# UART.net
KiCad netlist of a schematic drawn in Altium Designer
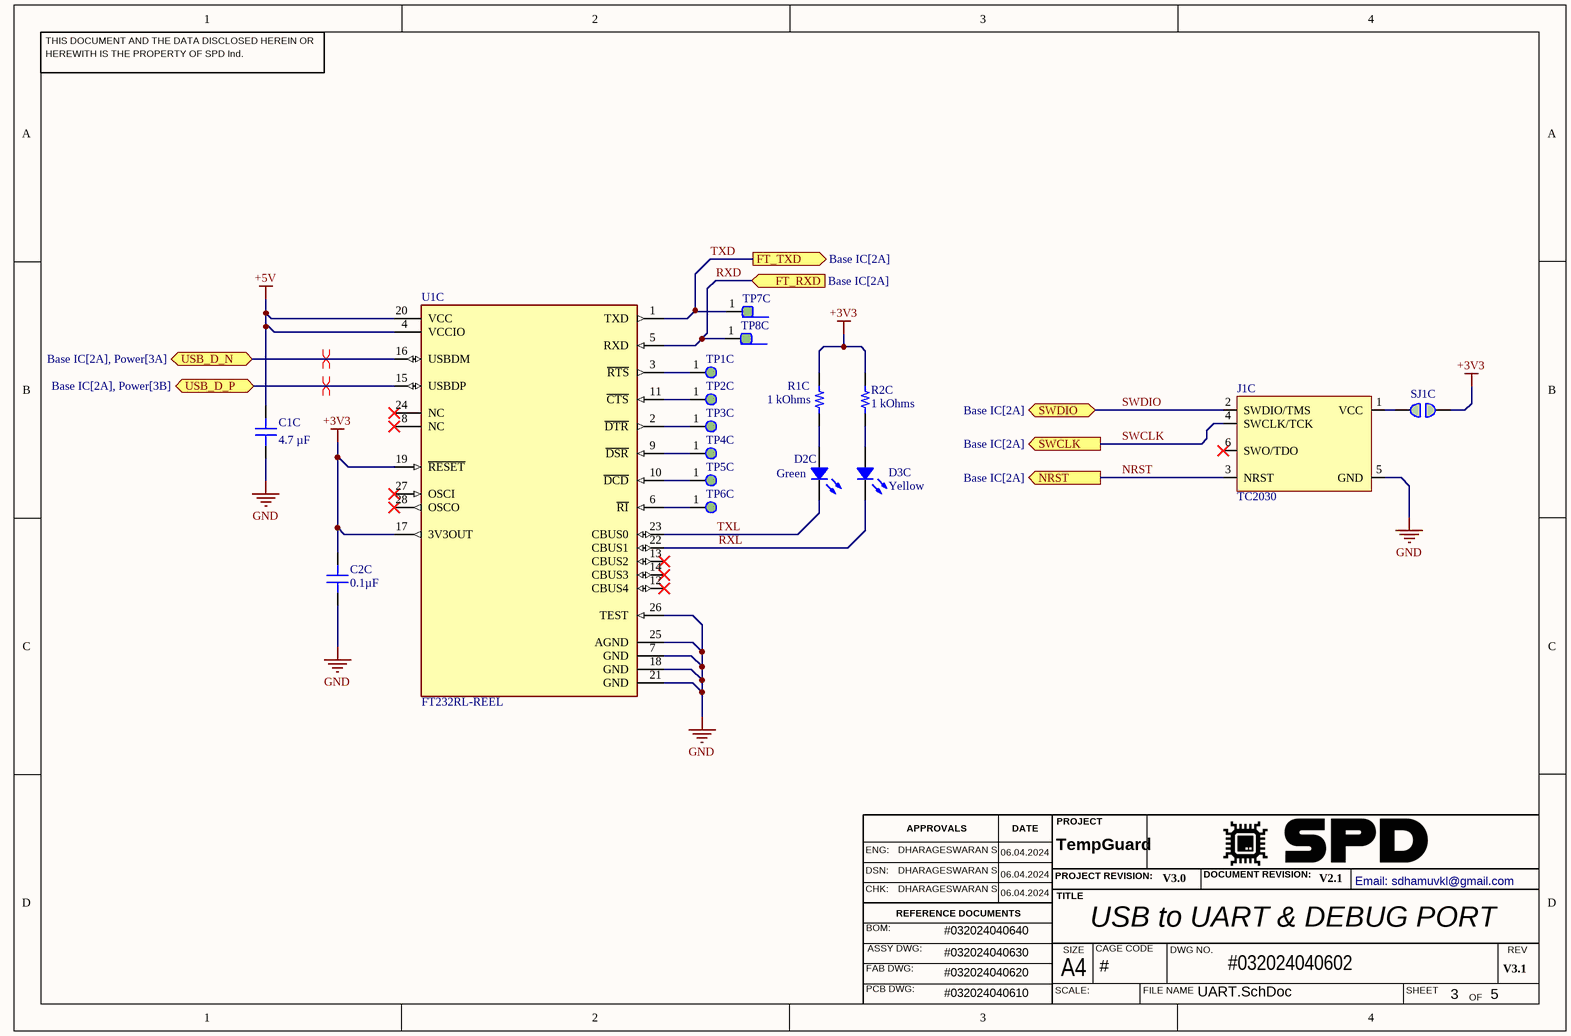
[diagram p0: UART.SchDoc]

(export (version "E")
  (design (tool "Eeschema 10.0.6"))
  (components
    (comp (ref "C1C")
      (value "4.7 µF")
      (footprint "CAP 0603_1608")
      (description "CAP CER 4.7UF 10V X7S 0603")
      (fields
        (field (name "PART NUMBER") "GRM188C71A475KE11D")
        (field (name "MANUFACTURER") "Murata Electronics")
      )
      (libsource (lib "Postgres Altium Library - altium_library") (part "Capacitor"))
    )
    (comp (ref "C2C")
      (value "0.1µF")
      (footprint "CAP 0603_1608")
      (description "CAP CER 0.1UF 10V X7R 0603")
      (fields (field (name "PART NUMBER") "LD03ZC104KAB2A") (field (name "MANUFACTURER") "AVX Corporation"))
      (libsource (lib "Postgres Altium Library - altium_library") (part "Capacitor"))
    )
    (comp (ref "D2C")
      (value "Green")
      (footprint "LED 0603_1608 GREEN")
      (description "LED GREEN CLEAR SMD")
      (fields
        (field (name "PART NUMBER") "SML-LXFP0603SUGCTR")
        (field (name "MANUFACTURER") "Lumex Opto/Components Inc.")
      )
      (libsource (lib "Postgres Altium Library - altium_library") (part "LED"))
    )
    (comp (ref "D3C")
      (value "Yellow")
      (footprint "LED 0603_1608 YELLOW")
      (description "LED YELLOW 0603 SMD")
      (fields
        (field (name "PART NUMBER") "VLMY1300-GS08")
        (field (name "MANUFACTURER") "Vishay Semiconductor Opto Division")
      )
      (libsource (lib "Postgres Altium Library - altium_library") (part "LED"))
    )
    (comp (ref "J1C")
      (value "TC2030")
      (footprint "TC2030-FP")
      (description "Tag-Connect No-Solder SWD Debug Connector DO NOT PLACE")
      (fields (field (name "MANUFACTURER") "Tag-Connect"))
      (libsource (lib "Integrated_Library1") (part "TC2030"))
    )
    (comp (ref "R1C")
      (value "1 kOhms")
      (footprint "RES 0603_1608")
      (description "RES SMD 1K OHM 0.1% 1/16W 0603")
      (fields (field (name "PART NUMBER") "CPF0603B1K0E") (field (name "TOLERANCE") "±0.1%"))
      (libsource (lib "Postgres Altium Library - altium_library") (part "Resistor"))
    )
    (comp (ref "R2C")
      (value "1 kOhms")
      (footprint "RES 0603_1608")
      (description "RES SMD 1K OHM 0.1% 1/16W 0603")
      (fields (field (name "PART NUMBER") "CPF0603B1K0E") (field (name "TOLERANCE") "±0.1%"))
      (libsource (lib "Postgres Altium Library - altium_library") (part "Resistor"))
    )
    (comp (ref "SJ1C")
      (value "2PIN")
      (footprint "Rounded Jumper")
      (libsource (lib "Jumper-SMD") (part "Rounded Jumper"))
    )
    (comp (ref "TP1C")
      (value "ROUND PAD 2MM")
      (footprint "ROUND PAD 2MM")
      (libsource (lib "TestPoints") (part "ROUND PAD 2MM"))
    )
    (comp (ref "TP2C")
      (value "ROUND PAD 2MM")
      (footprint "ROUND PAD 2MM")
      (libsource (lib "TestPoints") (part "ROUND PAD 2MM"))
    )
    (comp (ref "TP3C")
      (value "ROUND PAD 2MM")
      (footprint "ROUND PAD 2MM")
      (libsource (lib "TestPoints") (part "ROUND PAD 2MM"))
    )
    (comp (ref "TP4C")
      (value "ROUND PAD 2MM")
      (footprint "ROUND PAD 2MM")
      (libsource (lib "TestPoints") (part "ROUND PAD 2MM"))
    )
    (comp (ref "TP5C")
      (value "ROUND PAD 2MM")
      (footprint "ROUND PAD 2MM")
      (libsource (lib "TestPoints") (part "ROUND PAD 2MM"))
    )
    (comp (ref "TP6C")
      (value "ROUND PAD 2MM")
      (footprint "ROUND PAD 2MM")
      (libsource (lib "TestPoints") (part "ROUND PAD 2MM"))
    )
    (comp (ref "TP7C")
      (value "SQUARE PAD 1.5MM")
      (footprint "SQUARE PAD 1.5MM")
      (libsource (lib "TestPoints") (part "SQUARE PAD 1.5MM"))
    )
    (comp (ref "TP8C")
      (value "SQUARE PAD 1.5MM")
      (footprint "SQUARE PAD 1.5MM")
      (libsource (lib "TestPoints") (part "SQUARE PAD 1.5MM"))
    )
    (comp (ref "U1C")
      (value "FT232RL-REEL")
      (footprint "FP-SSOP-28-MFG")
      (description "IC USB FS SERIAL UART 28-SSOP")
      (fields (field (name "VOLTAGE") "5V"))
      (libsource (lib "Altium Content Vault") (part "fa727c664f4d88ca0f1b580aa0dd901"))
    )
  )
  (nets
    (net (code "1") (name "+3V3") (class "Default")
      (node (ref "C2C") (pin "2") (pinfunction "2_2") (pintype "passive"))
      (node (ref "R1C") (pin "2") (pinfunction "2_2") (pintype "passive"))
      (node (ref "R2C") (pin "2") (pinfunction "2_2") (pintype "passive"))
      (node (ref "SJ1C") (pin "2") (pinfunction "2_2") (pintype "passive"))
      (node (ref "U1C") (pin "17") (pinfunction "3V3OUT_17") (pintype "output"))
      (node (ref "U1C") (pin "19") (pinfunction "~{RESET}_19") (pintype "input"))
    )
    (net (code "2") (name "+5V") (class "Default")
      (node (ref "C1C") (pin "2") (pinfunction "2_2") (pintype "passive"))
      (node (ref "U1C") (pin "20") (pinfunction "VCC_20") (pintype "power_in"))
      (node (ref "U1C") (pin "4") (pinfunction "VCCIO_4") (pintype "power_in"))
    )
    (net (code "4") (name "/NRST") (class "Default")
      (node (ref "J1C") (pin "3") (pinfunction "NRST_3") (pintype "passive"))
    )
    (net (code "5") (name "/RXD") (class "Default")
      (node (ref "TP8C") (pin "1") (pinfunction "1_1") (pintype "passive"))
      (node (ref "U1C") (pin "5") (pinfunction "RXD_5") (pintype "input"))
    )
    (net (code "6") (name "/RXL") (class "Default")
      (node (ref "D3C") (pin "2") (pinfunction "2_2") (pintype "passive"))
      (node (ref "U1C") (pin "22") (pinfunction "CBUS1_22") (pintype "bidirectional"))
    )
    (net (code "7") (name "/SWCLK") (class "Default")
      (node (ref "J1C") (pin "4") (pinfunction "SWCLK/TCK_4") (pintype "passive"))
    )
    (net (code "8") (name "/SWDIO") (class "Default")
      (node (ref "J1C") (pin "2") (pinfunction "SWDIO/TMS_2") (pintype "passive"))
    )
    (net (code "9") (name "/TXD") (class "Default")
      (node (ref "TP7C") (pin "1") (pinfunction "1_1") (pintype "passive"))
      (node (ref "U1C") (pin "1") (pinfunction "TXD_1") (pintype "output"))
    )
    (net (code "10") (name "/TXL") (class "Default")
      (node (ref "D2C") (pin "2") (pinfunction "2_2") (pintype "passive"))
      (node (ref "U1C") (pin "23") (pinfunction "CBUS0_23") (pintype "bidirectional"))
    )
    (net (code "11") (name "/USB_D_N") (class "Default")
      (node (ref "U1C") (pin "16") (pinfunction "USBDM_16") (pintype "bidirectional"))
    )
    (net (code "12") (name "/USB_D_P") (class "Default")
      (node (ref "U1C") (pin "15") (pinfunction "USBDP_15") (pintype "bidirectional"))
    )
    (net (code "13") (name "GND") (class "Default")
      (node (ref "C1C") (pin "1") (pinfunction "1_1") (pintype "passive"))
      (node (ref "C2C") (pin "1") (pinfunction "1_1") (pintype "passive"))
      (node (ref "J1C") (pin "5") (pinfunction "GND_5") (pintype "passive"))
      (node (ref "U1C") (pin "18") (pinfunction "GND_18") (pintype "power_in"))
      (node (ref "U1C") (pin "21") (pinfunction "GND_21") (pintype "power_in"))
      (node (ref "U1C") (pin "25") (pinfunction "AGND_25") (pintype "power_in"))
      (node (ref "U1C") (pin "26") (pinfunction "TEST_26") (pintype "input"))
      (node (ref "U1C") (pin "7") (pinfunction "GND_7") (pintype "power_in"))
    )
    (net (code "14") (name "Net-(D2C-Pad1)") (class "Default")
      (node (ref "D2C") (pin "1") (pinfunction "1_1") (pintype "passive"))
      (node (ref "R1C") (pin "1") (pinfunction "1_1") (pintype "passive"))
    )
    (net (code "15") (name "Net-(D3C-Pad1)") (class "Default")
      (node (ref "D3C") (pin "1") (pinfunction "1_1") (pintype "passive"))
      (node (ref "R2C") (pin "1") (pinfunction "1_1") (pintype "passive"))
    )
    (net (code "16") (name "Net-(J1C-VCC)") (class "Default")
      (node (ref "J1C") (pin "1") (pinfunction "VCC_1") (pintype "passive"))
      (node (ref "SJ1C") (pin "1") (pinfunction "1_1") (pintype "passive"))
    )
    (net (code "17") (name "Net-(U1C-~{CTS})") (class "Default")
      (node (ref "TP2C") (pin "1") (pinfunction "1_1") (pintype "passive"))
      (node (ref "U1C") (pin "11") (pinfunction "~{CTS}_11") (pintype "input"))
    )
    (net (code "18") (name "Net-(U1C-~{DCD})") (class "Default")
      (node (ref "TP5C") (pin "1") (pinfunction "1_1") (pintype "passive"))
      (node (ref "U1C") (pin "10") (pinfunction "~{DCD}_10") (pintype "input"))
    )
    (net (code "19") (name "Net-(U1C-~{DSR})") (class "Default")
      (node (ref "TP4C") (pin "1") (pinfunction "1_1") (pintype "passive"))
      (node (ref "U1C") (pin "9") (pinfunction "~{DSR}_9") (pintype "input"))
    )
    (net (code "20") (name "Net-(U1C-~{DTR})") (class "Default")
      (node (ref "TP3C") (pin "1") (pinfunction "1_1") (pintype "passive"))
      (node (ref "U1C") (pin "2") (pinfunction "~{DTR}_2") (pintype "output"))
    )
    (net (code "21") (name "Net-(U1C-~{RI})") (class "Default")
      (node (ref "TP6C") (pin "1") (pinfunction "1_1") (pintype "passive"))
      (node (ref "U1C") (pin "6") (pinfunction "~{RI}_6") (pintype "input"))
    )
    (net (code "22") (name "Net-(U1C-~{RTS})") (class "Default")
      (node (ref "TP1C") (pin "1") (pinfunction "1_1") (pintype "passive"))
      (node (ref "U1C") (pin "3") (pinfunction "~{RTS}_3") (pintype "output"))
    )
    (net (code "23") (name "unconnected-(J1C-SWO{slash}TDO-Pad6)") (class "Default")
      (node (ref "J1C") (pin "6") (pinfunction "SWO/TDO_6") (pintype "passive+no_connect"))
    )
    (net (code "24") (name "unconnected-(U1C-CBUS2-Pad13)") (class "Default")
      (node (ref "U1C") (pin "13") (pinfunction "CBUS2_13") (pintype "bidirectional+no_connect"))
    )
    (net (code "25") (name "unconnected-(U1C-CBUS3-Pad14)") (class "Default")
      (node (ref "U1C") (pin "14") (pinfunction "CBUS3_14") (pintype "bidirectional+no_connect"))
    )
    (net (code "26") (name "unconnected-(U1C-CBUS4-Pad12)") (class "Default")
      (node (ref "U1C") (pin "12") (pinfunction "CBUS4_12") (pintype "bidirectional+no_connect"))
    )
    (net (code "27") (name "unconnected-(U1C-NC-Pad8)") (class "Default")
      (node (ref "U1C") (pin "8") (pinfunction "NC_8") (pintype "passive+no_connect"))
    )
    (net (code "28") (name "unconnected-(U1C-NC-Pad24)") (class "Default")
      (node (ref "U1C") (pin "24") (pinfunction "NC_24") (pintype "passive+no_connect"))
    )
    (net (code "29") (name "unconnected-(U1C-OSCI-Pad27)") (class "Default")
      (node (ref "U1C") (pin "27") (pinfunction "OSCI_27") (pintype "input+no_connect"))
    )
    (net (code "30") (name "unconnected-(U1C-OSCO-Pad28)") (class "Default")
      (node (ref "U1C") (pin "28") (pinfunction "OSCO_28") (pintype "output+no_connect"))
    )
  )
)
